# 2_FPGAIO.net
KiCad netlist of a schematic drawn in Altium Designer
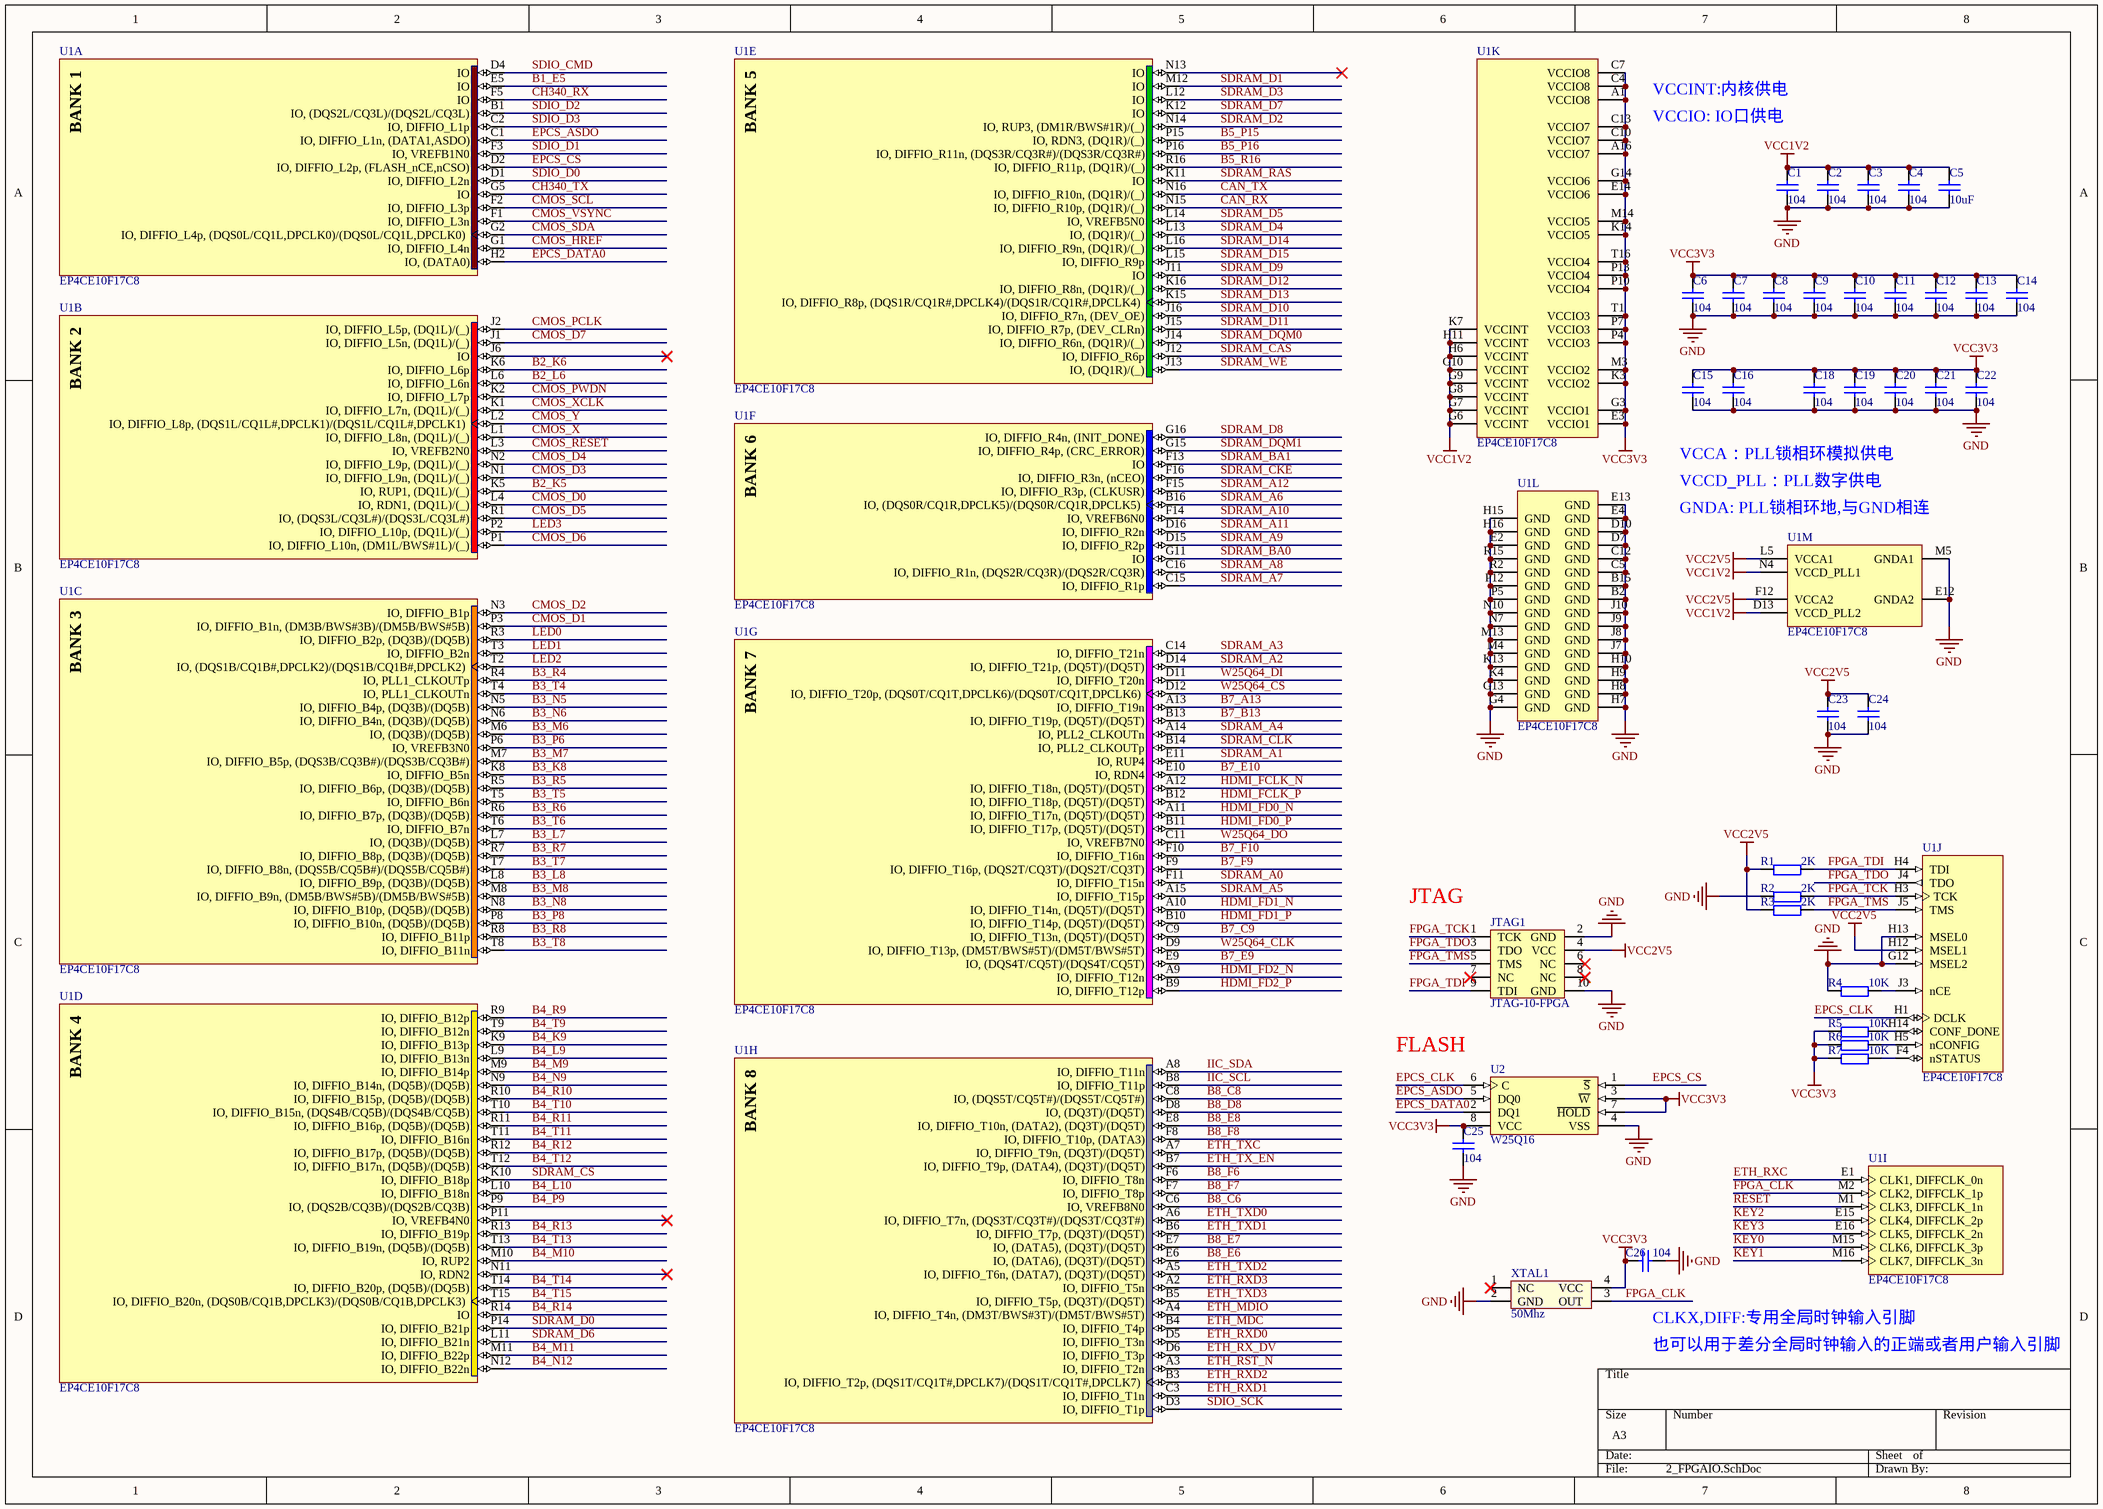
[diagram p0: 2_FPGAIO.SchDoc]

(export (version "E")
  (design (tool "Eeschema 10.0.6"))
  (components
    (comp (ref "C1")
      (value "104")
      (footprint "C 0402")
      (libsource (lib "ATK-DFPGL25G&50G_V1.3") (part "C-0603-SMD"))
    )
    (comp (ref "C2")
      (value "104")
      (footprint "C 0402")
      (libsource (lib "ATK-DFPGL25G&50G_V1.3") (part "C-0603-SMD"))
    )
    (comp (ref "C3")
      (value "104")
      (footprint "C 0402")
      (libsource (lib "ATK-DFPGL25G&50G_V1.3") (part "C-0603-SMD"))
    )
    (comp (ref "C4")
      (value "104")
      (footprint "C 0402")
      (libsource (lib "ATK-DFPGL25G&50G_V1.3") (part "C-0603-SMD"))
    )
    (comp (ref "C5")
      (value "10uF")
      (footprint "C 0402")
      (libsource (lib "ATK-DFPGL25G&50G_V1.3") (part "C-0603-SMD"))
    )
    (comp (ref "C6")
      (value "104")
      (footprint "C 0402")
      (libsource (lib "ATK-DFPGL25G&50G_V1.3") (part "C-0603-SMD"))
    )
    (comp (ref "C7")
      (value "104")
      (footprint "C 0402")
      (libsource (lib "ATK-DFPGL25G&50G_V1.3") (part "C-0603-SMD"))
    )
    (comp (ref "C8")
      (value "104")
      (footprint "C 0402")
      (libsource (lib "ATK-DFPGL25G&50G_V1.3") (part "C-0603-SMD"))
    )
    (comp (ref "C9")
      (value "104")
      (footprint "C 0402")
      (libsource (lib "ATK-DFPGL25G&50G_V1.3") (part "C-0603-SMD"))
    )
    (comp (ref "C10")
      (value "104")
      (footprint "C 0402")
      (libsource (lib "ATK-DFPGL25G&50G_V1.3") (part "C-0603-SMD"))
    )
    (comp (ref "C11")
      (value "104")
      (footprint "C 0402")
      (libsource (lib "ATK-DFPGL25G&50G_V1.3") (part "C-0603-SMD"))
    )
    (comp (ref "C12")
      (value "104")
      (footprint "C 0402")
      (libsource (lib "ATK-DFPGL25G&50G_V1.3") (part "C-0603-SMD"))
    )
    (comp (ref "C13")
      (value "104")
      (footprint "C 0402")
      (libsource (lib "ATK-DFPGL25G&50G_V1.3") (part "C-0603-SMD"))
    )
    (comp (ref "C14")
      (value "104")
      (footprint "C 0402")
      (libsource (lib "ATK-DFPGL25G&50G_V1.3") (part "C-0603-SMD"))
    )
    (comp (ref "C15")
      (value "104")
      (footprint "C 0402")
      (libsource (lib "ATK-DFPGL25G&50G_V1.3") (part "C-0603-SMD"))
    )
    (comp (ref "C16")
      (value "104")
      (footprint "C 0402")
      (libsource (lib "ATK-DFPGL25G&50G_V1.3") (part "C-0603-SMD"))
    )
    (comp (ref "C18")
      (value "104")
      (footprint "C 0402")
      (libsource (lib "ATK-DFPGL25G&50G_V1.3") (part "C-0603-SMD"))
    )
    (comp (ref "C19")
      (value "104")
      (footprint "C 0402")
      (libsource (lib "ATK-DFPGL25G&50G_V1.3") (part "C-0603-SMD"))
    )
    (comp (ref "C20")
      (value "104")
      (footprint "C 0402")
      (libsource (lib "ATK-DFPGL25G&50G_V1.3") (part "C-0603-SMD"))
    )
    (comp (ref "C21")
      (value "104")
      (footprint "C 0402")
      (libsource (lib "ATK-DFPGL25G&50G_V1.3") (part "C-0603-SMD"))
    )
    (comp (ref "C22")
      (value "104")
      (footprint "C 0402")
      (libsource (lib "ATK-DFPGL25G&50G_V1.3") (part "C-0603-SMD"))
    )
    (comp (ref "C23")
      (value "104")
      (footprint "C 0402")
      (libsource (lib "ATK-DFPGL25G&50G_V1.3") (part "C-0603-SMD"))
    )
    (comp (ref "C24")
      (value "104")
      (footprint "C 0402")
      (libsource (lib "ATK-DFPGL25G&50G_V1.3") (part "C-0603-SMD"))
    )
    (comp (ref "C25")
      (value "104")
      (footprint "C 0603")
      (libsource (lib "ATK-DFPGL25G&50G_V1.3") (part "C-0603-SMD"))
    )
    (comp (ref "C26")
      (value "104")
      (footprint "C 0603")
      (libsource (lib "ATK-DFPGL25G&50G_V1.3") (part "C-0603-SMD"))
    )
    (comp (ref "JTAG1")
      (value "JTAG-10-FPGA")
      (footprint "JTAG座_弯角_2x5")
      (libsource (lib "PIONEER") (part "JTAG-10-FPGA"))
    )
    (comp (ref "R1") (value "2K") (footprint "R 0402") (libsource (lib "PIONEER") (part "R")))
    (comp (ref "R2") (value "2K") (footprint "R 0402") (libsource (lib "PIONEER") (part "R")))
    (comp (ref "R3") (value "2K") (footprint "R 0402") (libsource (lib "PIONEER") (part "R")))
    (comp (ref "R4") (value "10K") (footprint "R 0402") (libsource (lib "PIONEER") (part "R")))
    (comp (ref "R5") (value "10K") (footprint "R 0402") (libsource (lib "PIONEER") (part "R")))
    (comp (ref "R6") (value "10K") (footprint "R 0402") (libsource (lib "PIONEER") (part "R")))
    (comp (ref "R7") (value "10K") (footprint "R 0402") (libsource (lib "PIONEER") (part "R")))
    (comp (ref "U1")
      (value "EP4CE10F17C8")
      (footprint "FBGA256")
      (fields (field (name "PUBLISHER") "Altium Limited"))
      (libsource (lib "PIONEER") (part "EP4CE6F17C8"))
    )
    (comp (ref "U2")
      (value "W25Q16")
      (footprint "SOIC-8_L5.3-W5.3-P1.27-LS8.0-BL")
      (description "16 Mb (x1) Automotive Serial NOR Flash Memory, 75 MHz, 2.7 to 3.6 V, 8-pin SO8")
      (fields (field (name "VOLTAGE") "2.7V-3.6V爭ISHIDDEN=T¦") (field (name "MANUFACTURER") "Micron"))
      (libsource (lib "PIONEER") (part "M25P16"))
    )
    (comp (ref "XTAL1")
      (value "50Mhz")
      (footprint "XTAL3225")
      (description "有源晶振")
      (libsource (lib "PIONEER") (part "XTAL_S"))
    )
  )
  (nets
    (net (code "1") (name "/B1_E5") (class "Default")
      (node (ref "U1") (pin "E5") (pinfunction "IO_E5") (pintype "bidirectional"))
    )
    (net (code "2") (name "/B2_K5") (class "Default")
      (node (ref "U1") (pin "K5") (pinfunction "IO,_RUP1,_(DQ1L)/(_)_K5") (pintype "bidirectional"))
    )
    (net (code "3") (name "/B2_K6") (class "Default")
      (node (ref "U1") (pin "K6") (pinfunction "IO,_DIFFIO_L6p_K6") (pintype "bidirectional"))
    )
    (net (code "4") (name "/B2_L6") (class "Default")
      (node (ref "U1") (pin "L6") (pinfunction "IO,_DIFFIO_L6n_L6") (pintype "bidirectional"))
    )
    (net (code "5") (name "/B3_K8") (class "Default")
      (node (ref "U1") (pin "K8") (pinfunction "IO,_DIFFIO_B5n_K8") (pintype "bidirectional"))
    )
    (net (code "6") (name "/B3_L7") (class "Default")
      (node (ref "U1") (pin "L7") (pinfunction "IO,_(DQ3B)/(DQ5B)_L7") (pintype "bidirectional"))
    )
    (net (code "7") (name "/B3_L8") (class "Default")
      (node (ref "U1") (pin "L8") (pinfunction "IO,_DIFFIO_B9p,_(DQ3B)/(DQ5B)_L8") (pintype "bidirectional"))
    )
    (net (code "8") (name "/B3_M6") (class "Default")
      (node (ref "U1") (pin "M6") (pinfunction "IO,_(DQ3B)/(DQ5B)_M6") (pintype "bidirectional"))
    )
    (net (code "9") (name "/B3_M7") (class "Default")
      (node (ref "U1") (pin "M7") (pinfunction "IO,_DIFFIO_B5p,_(DQS3B/CQ3B#)/(DQS3B/CQ3B#)_M7") (pintype "bidirectional"))
    )
    (net (code "10") (name "/B3_M8") (class "Default")
      (node (ref "U1") (pin "M8") (pinfunction "IO,_DIFFIO_B9n,_(DM5B/BWS#5B)/(DM5B/BWS#5B)_M8") (pintype "bidirectional"))
    )
    (net (code "11") (name "/B3_N5") (class "Default")
      (node (ref "U1") (pin "N5") (pinfunction "IO,_DIFFIO_B4p,_(DQ3B)/(DQ5B)_N5") (pintype "bidirectional"))
    )
    (net (code "12") (name "/B3_N6") (class "Default")
      (node (ref "U1") (pin "N6") (pinfunction "IO,_DIFFIO_B4n,_(DQ3B)/(DQ5B)_N6") (pintype "bidirectional"))
    )
    (net (code "13") (name "/B3_N8") (class "Default")
      (node (ref "U1") (pin "N8") (pinfunction "IO,_DIFFIO_B10p,_(DQ5B)/(DQ5B)_N8") (pintype "bidirectional"))
    )
    (net (code "14") (name "/B3_P6") (class "Default")
      (node (ref "U1") (pin "P6") (pinfunction "IO,_VREFB3N0_P6") (pintype "bidirectional"))
    )
    (net (code "15") (name "/B3_P8") (class "Default")
      (node (ref "U1") (pin "P8") (pinfunction "IO,_DIFFIO_B10n,_(DQ5B)/(DQ5B)_P8") (pintype "bidirectional"))
    )
    (net (code "16") (name "/B3_R4") (class "Default")
      (node (ref "U1") (pin "R4") (pinfunction "IO,_PLL1_CLKOUTp_R4") (pintype "bidirectional"))
    )
    (net (code "17") (name "/B3_R5") (class "Default")
      (node (ref "U1") (pin "R5") (pinfunction "IO,_DIFFIO_B6p,_(DQ3B)/(DQ5B)_R5") (pintype "bidirectional"))
    )
    (net (code "18") (name "/B3_R6") (class "Default")
      (node (ref "U1") (pin "R6") (pinfunction "IO,_DIFFIO_B7p,_(DQ3B)/(DQ5B)_R6") (pintype "bidirectional"))
    )
    (net (code "19") (name "/B3_R7") (class "Default")
      (node (ref "U1") (pin "R7") (pinfunction "IO,_DIFFIO_B8p,_(DQ3B)/(DQ5B)_R7") (pintype "bidirectional"))
    )
    (net (code "20") (name "/B3_R8") (class "Default")
      (node (ref "U1") (pin "R8") (pinfunction "IO,_DIFFIO_B11p_R8") (pintype "bidirectional"))
    )
    (net (code "21") (name "/B3_T4") (class "Default")
      (node (ref "U1") (pin "T4") (pinfunction "IO,_PLL1_CLKOUTn_T4") (pintype "bidirectional"))
    )
    (net (code "22") (name "/B3_T5") (class "Default")
      (node (ref "U1") (pin "T5") (pinfunction "IO,_DIFFIO_B6n_T5") (pintype "bidirectional"))
    )
    (net (code "23") (name "/B3_T6") (class "Default")
      (node (ref "U1") (pin "T6") (pinfunction "IO,_DIFFIO_B7n_T6") (pintype "bidirectional"))
    )
    (net (code "24") (name "/B3_T7") (class "Default")
      (node (ref "U1") (pin "T7") (pinfunction "IO,_DIFFIO_B8n,_(DQS5B/CQ5B#)/(DQS5B/CQ5B#)_T7") (pintype "bidirectional"))
    )
    (net (code "25") (name "/B3_T8") (class "Default")
      (node (ref "U1") (pin "T8") (pinfunction "IO,_DIFFIO_B11n_T8") (pintype "bidirectional"))
    )
    (net (code "26") (name "/B4_K9") (class "Default")
      (node (ref "U1") (pin "K9") (pinfunction "IO,_DIFFIO_B13p_K9") (pintype "bidirectional"))
    )
    (net (code "27") (name "/B4_L9") (class "Default")
      (node (ref "U1") (pin "L9") (pinfunction "IO,_DIFFIO_B13n_L9") (pintype "bidirectional"))
    )
    (net (code "28") (name "/B4_L10") (class "Default")
      (node (ref "U1") (pin "L10") (pinfunction "IO,_DIFFIO_B18n_L10") (pintype "bidirectional"))
    )
    (net (code "29") (name "/B4_M9") (class "Default")
      (node (ref "U1") (pin "M9") (pinfunction "IO,_DIFFIO_B14p_M9") (pintype "bidirectional"))
    )
    (net (code "30") (name "/B4_M10") (class "Default")
      (node (ref "U1") (pin "M10") (pinfunction "IO,_RUP2_M10") (pintype "bidirectional"))
    )
    (net (code "31") (name "/B4_M11") (class "Default")
      (node (ref "U1") (pin "M11") (pinfunction "IO,_DIFFIO_B22p_M11") (pintype "bidirectional"))
    )
    (net (code "32") (name "/B4_N9") (class "Default")
      (node (ref "U1") (pin "N9") (pinfunction "IO,_DIFFIO_B14n,_(DQ5B)/(DQ5B)_N9") (pintype "bidirectional"))
    )
    (net (code "33") (name "/B4_N12") (class "Default")
      (node (ref "U1") (pin "N12") (pinfunction "IO,_DIFFIO_B22n_N12") (pintype "bidirectional"))
    )
    (net (code "34") (name "/B4_P9") (class "Default")
      (node (ref "U1") (pin "P9") (pinfunction "IO,_(DQS2B/CQ3B)/(DQS2B/CQ3B)_P9") (pintype "bidirectional"))
    )
    (net (code "35") (name "/B4_R9") (class "Default")
      (node (ref "U1") (pin "R9") (pinfunction "IO,_DIFFIO_B12p_R9") (pintype "bidirectional"))
    )
    (net (code "36") (name "/B4_R10") (class "Default")
      (node (ref "U1") (pin "R10") (pinfunction "IO,_DIFFIO_B15p,_(DQ5B)/(DQ5B)_R10") (pintype "bidirectional"))
    )
    (net (code "37") (name "/B4_R11") (class "Default")
      (node (ref "U1") (pin "R11") (pinfunction "IO,_DIFFIO_B16p,_(DQ5B)/(DQ5B)_R11") (pintype "bidirectional"))
    )
    (net (code "38") (name "/B4_R12") (class "Default")
      (node (ref "U1") (pin "R12") (pinfunction "IO,_DIFFIO_B17p,_(DQ5B)/(DQ5B)_R12") (pintype "bidirectional"))
    )
    (net (code "39") (name "/B4_R13") (class "Default")
      (node (ref "U1") (pin "R13") (pinfunction "IO,_DIFFIO_B19p_R13") (pintype "bidirectional"))
    )
    (net (code "40") (name "/B4_R14") (class "Default")
      (node (ref "U1") (pin "R14") (pinfunction "IO_R14") (pintype "bidirectional"))
    )
    (net (code "41") (name "/B4_T9") (class "Default")
      (node (ref "U1") (pin "T9") (pinfunction "IO,_DIFFIO_B12n_T9") (pintype "bidirectional"))
    )
    (net (code "42") (name "/B4_T10") (class "Default")
      (node (ref "U1") (pin "T10") (pinfunction "IO,_DIFFIO_B15n,_(DQS4B/CQ5B)/(DQS4B/CQ5B)_T10") (pintype "bidirectional"))
    )
    (net (code "43") (name "/B4_T11") (class "Default")
      (node (ref "U1") (pin "T11") (pinfunction "IO,_DIFFIO_B16n_T11") (pintype "bidirectional"))
    )
    (net (code "44") (name "/B4_T12") (class "Default")
      (node (ref "U1") (pin "T12") (pinfunction "IO,_DIFFIO_B17n,_(DQ5B)/(DQ5B)_T12") (pintype "bidirectional"))
    )
    (net (code "45") (name "/B4_T13") (class "Default")
      (node (ref "U1") (pin "T13") (pinfunction "IO,_DIFFIO_B19n,_(DQ5B)/(DQ5B)_T13") (pintype "bidirectional"))
    )
    (net (code "46") (name "/B4_T14") (class "Default")
      (node (ref "U1") (pin "T14") (pinfunction "IO,_DIFFIO_B20p,_(DQ5B)/(DQ5B)_T14") (pintype "bidirectional"))
    )
    (net (code "47") (name "/B4_T15") (class "Default")
      (node (ref "U1") (pin "T15") (pinfunction "IO,_DIFFIO_B20n,_(DQS0B/CQ1B,DPCLK3)/(DQS0B/CQ1B,DPCLK3)_T15") (pintype "bidirectional"))
    )
    (net (code "48") (name "/B5_P15") (class "Default")
      (node (ref "U1") (pin "P15") (pinfunction "IO,_RDN3,_(DQ1R)/(_)_P15") (pintype "bidirectional"))
    )
    (net (code "49") (name "/B5_P16") (class "Default")
      (node (ref "U1") (pin "P16") (pinfunction "IO,_DIFFIO_R11n,_(DQS3R/CQ3R#)/(DQS3R/CQ3R#)_P16") (pintype "bidirectional"))
    )
    (net (code "50") (name "/B5_R16") (class "Default")
      (node (ref "U1") (pin "R16") (pinfunction "IO,_DIFFIO_R11p,_(DQ1R)/(_)_R16") (pintype "bidirectional"))
    )
    (net (code "51") (name "/B7_A13") (class "Default")
      (node (ref "U1") (pin "A13") (pinfunction "IO,_DIFFIO_T19n_A13") (pintype "bidirectional"))
    )
    (net (code "52") (name "/B7_B13") (class "Default")
      (node (ref "U1") (pin "B13") (pinfunction "IO,_DIFFIO_T19p,_(DQ5T)/(DQ5T)_B13") (pintype "bidirectional"))
    )
    (net (code "53") (name "/B7_C9") (class "Default")
      (node (ref "U1") (pin "C9") (pinfunction "IO,_DIFFIO_T13n,_(DQ5T)/(DQ5T)_C9") (pintype "bidirectional"))
    )
    (net (code "54") (name "/B7_E9") (class "Default")
      (node (ref "U1") (pin "E9") (pinfunction "IO,_(DQS4T/CQ5T)/(DQS4T/CQ5T)_E9") (pintype "bidirectional"))
    )
    (net (code "55") (name "/B7_E10") (class "Default")
      (node (ref "U1") (pin "E10") (pinfunction "IO,_RDN4_E10") (pintype "bidirectional"))
    )
    (net (code "56") (name "/B7_F9") (class "Default")
      (node (ref "U1") (pin "F9") (pinfunction "IO,_DIFFIO_T16p,_(DQS2T/CQ3T)/(DQS2T/CQ3T)_F9") (pintype "bidirectional"))
    )
    (net (code "57") (name "/B7_F10") (class "Default")
      (node (ref "U1") (pin "F10") (pinfunction "IO,_DIFFIO_T16n_F10") (pintype "bidirectional"))
    )
    (net (code "58") (name "/B8_C6") (class "Default")
      (node (ref "U1") (pin "C6") (pinfunction "IO,_VREFB8N0_C6") (pintype "bidirectional"))
    )
    (net (code "59") (name "/B8_C8") (class "Default")
      (node (ref "U1") (pin "C8") (pinfunction "IO,_(DQS5T/CQ5T#)/(DQS5T/CQ5T#)_C8") (pintype "bidirectional"))
    )
    (net (code "60") (name "/B8_D8") (class "Default")
      (node (ref "U1") (pin "D8") (pinfunction "IO,_(DQ3T)/(DQ5T)_D8") (pintype "bidirectional"))
    )
    (net (code "61") (name "/B8_E6") (class "Default")
      (node (ref "U1") (pin "E6") (pinfunction "IO,_(DATA6),_(DQ3T)/(DQ5T)_E6") (pintype "bidirectional"))
    )
    (net (code "62") (name "/B8_E7") (class "Default")
      (node (ref "U1") (pin "E7") (pinfunction "IO,_(DATA5),_(DQ3T)/(DQ5T)_E7") (pintype "bidirectional"))
    )
    (net (code "63") (name "/B8_E8") (class "Default")
      (node (ref "U1") (pin "E8") (pinfunction "IO,_DIFFIO_T10n,_(DATA2),_(DQ3T)/(DQ5T)_E8") (pintype "bidirectional"))
    )
    (net (code "64") (name "/B8_F6") (class "Default")
      (node (ref "U1") (pin "F6") (pinfunction "IO,_DIFFIO_T8n_F6") (pintype "bidirectional"))
    )
    (net (code "65") (name "/B8_F7") (class "Default")
      (node (ref "U1") (pin "F7") (pinfunction "IO,_DIFFIO_T8p_F7") (pintype "bidirectional"))
    )
    (net (code "66") (name "/B8_F8") (class "Default")
      (node (ref "U1") (pin "F8") (pinfunction "IO,_DIFFIO_T10p,_(DATA3)_F8") (pintype "bidirectional"))
    )
    (net (code "67") (name "/CAN_RX") (class "Default")
      (node (ref "U1") (pin "N15") (pinfunction "IO,_DIFFIO_R10p,_(DQ1R)/(_)_N15") (pintype "bidirectional"))
    )
    (net (code "68") (name "/CAN_TX") (class "Default")
      (node (ref "U1") (pin "N16") (pinfunction "IO,_DIFFIO_R10n,_(DQ1R)/(_)_N16") (pintype "bidirectional"))
    )
    (net (code "69") (name "/CH340_RX") (class "Default")
      (node (ref "U1") (pin "F5") (pinfunction "IO_F5") (pintype "bidirectional"))
    )
    (net (code "70") (name "/CH340_TX") (class "Default")
      (node (ref "U1") (pin "G5") (pinfunction "IO_G5") (pintype "bidirectional"))
    )
    (net (code "71") (name "/CMOS_D0") (class "Default")
      (node (ref "U1") (pin "L4") (pinfunction "IO,_RDN1,_(DQ1L)/(_)_L4") (pintype "bidirectional"))
    )
    (net (code "72") (name "/CMOS_D1") (class "Default")
      (node (ref "U1") (pin "P3") (pinfunction "IO,_DIFFIO_B1n,_(DM3B/BWS#3B)/(DM5B/BWS#5B)_P3") (pintype "bidirectional"))
    )
    (net (code "73") (name "/CMOS_D2") (class "Default")
      (node (ref "U1") (pin "N3") (pinfunction "IO,_DIFFIO_B1p_N3") (pintype "bidirectional"))
    )
    (net (code "74") (name "/CMOS_D3") (class "Default")
      (node (ref "U1") (pin "N1") (pinfunction "IO,_DIFFIO_L9n,_(DQ1L)/(_)_N1") (pintype "bidirectional"))
    )
    (net (code "75") (name "/CMOS_D4") (class "Default")
      (node (ref "U1") (pin "N2") (pinfunction "IO,_DIFFIO_L9p,_(DQ1L)/(_)_N2") (pintype "bidirectional"))
    )
    (net (code "76") (name "/CMOS_D5") (class "Default")
      (node (ref "U1") (pin "R1") (pinfunction "IO,_(DQS3L/CQ3L#)/(DQS3L/CQ3L#)_R1") (pintype "bidirectional"))
    )
    (net (code "77") (name "/CMOS_D6") (class "Default")
      (node (ref "U1") (pin "P1") (pinfunction "IO,_DIFFIO_L10n,_(DM1L/BWS#1L)/(_)_P1") (pintype "bidirectional"))
    )
    (net (code "78") (name "/CMOS_D7") (class "Default")
      (node (ref "U1") (pin "J1") (pinfunction "IO,_DIFFIO_L5n,_(DQ1L)/(_)_J1") (pintype "bidirectional"))
    )
    (net (code "79") (name "/CMOS_HREF") (class "Default")
      (node (ref "U1") (pin "G1") (pinfunction "IO,_DIFFIO_L4n_G1") (pintype "bidirectional"))
    )
    (net (code "80") (name "/CMOS_PCLK") (class "Default")
      (node (ref "U1") (pin "J2") (pinfunction "IO,_DIFFIO_L5p,_(DQ1L)/(_)_J2") (pintype "bidirectional"))
    )
    (net (code "81") (name "/CMOS_PWDN") (class "Default")
      (node (ref "U1") (pin "K2") (pinfunction "IO,_DIFFIO_L7p_K2") (pintype "bidirectional"))
    )
    (net (code "82") (name "/CMOS_RESET") (class "Default")
      (node (ref "U1") (pin "L3") (pinfunction "IO,_VREFB2N0_L3") (pintype "bidirectional"))
    )
    (net (code "83") (name "/CMOS_SCL") (class "Default")
      (node (ref "U1") (pin "F2") (pinfunction "IO,_DIFFIO_L3p_F2") (pintype "bidirectional"))
    )
    (net (code "84") (name "/CMOS_SDA") (class "Default")
      (node (ref "U1") (pin "G2") (pinfunction "IO,_DIFFIO_L4p,_(DQS0L/CQ1L,DPCLK0)/(DQS0L/CQ1L,DPCLK0)_G2") (pintype "bidirectional"))
    )
    (net (code "85") (name "/CMOS_VSYNC") (class "Default")
      (node (ref "U1") (pin "F1") (pinfunction "IO,_DIFFIO_L3n_F1") (pintype "bidirectional"))
    )
    (net (code "86") (name "/CMOS_X") (class "Default")
      (node (ref "U1") (pin "L1") (pinfunction "IO,_DIFFIO_L8n,_(DQ1L)/(_)_L1") (pintype "bidirectional"))
    )
    (net (code "87") (name "/CMOS_XCLK") (class "Default")
      (node (ref "U1") (pin "K1") (pinfunction "IO,_DIFFIO_L7n,_(DQ1L)/(_)_K1") (pintype "bidirectional"))
    )
    (net (code "88") (name "/CMOS_Y") (class "Default")
      (node (ref "U1") (pin "L2") (pinfunction "IO,_DIFFIO_L8p,_(DQS1L/CQ1L#,DPCLK1)/(DQS1L/CQ1L#,DPCLK1)_L2") (pintype "bidirectional"))
    )
    (net (code "89") (name "/EPCS_ASDO") (class "Default")
      (node (ref "U1") (pin "C1") (pinfunction "IO,_DIFFIO_L1n,_(DATA1,ASDO)_C1") (pintype "bidirectional"))
      (node (ref "U2") (pin "5") (pinfunction "DQ0_5") (pintype "input"))
    )
    (net (code "90") (name "/EPCS_CLK") (class "Default")
      (node (ref "U1") (pin "H1") (pinfunction "DCLK_H1") (pintype "bidirectional"))
      (node (ref "U2") (pin "6") (pinfunction "C_6") (pintype "input"))
    )
    (net (code "91") (name "/EPCS_CS") (class "Default")
      (node (ref "U1") (pin "D2") (pinfunction "IO,_DIFFIO_L2p,_(FLASH_nCE,nCSO)_D2") (pintype "bidirectional"))
      (node (ref "U2") (pin "1") (pinfunction "~{S}_1") (pintype "input"))
    )
    (net (code "92") (name "/EPCS_DATA0") (class "Default")
      (node (ref "U1") (pin "H2") (pinfunction "IO,_(DATA0)_H2") (pintype "bidirectional"))
      (node (ref "U2") (pin "2") (pinfunction "DQ1_2") (pintype "tri_state"))
    )
    (net (code "93") (name "/ETH_MDC") (class "Default")
      (node (ref "U1") (pin "B4") (pinfunction "IO,_DIFFIO_T4p_B4") (pintype "bidirectional"))
    )
    (net (code "94") (name "/ETH_MDIO") (class "Default")
      (node (ref "U1") (pin "A4") (pinfunction "IO,_DIFFIO_T4n,_(DM3T/BWS#3T)/(DM5T/BWS#5T)_A4") (pintype "bidirectional"))
    )
    (net (code "95") (name "/ETH_RST_N") (class "Default")
      (node (ref "U1") (pin "A3") (pinfunction "IO,_DIFFIO_T2n_A3") (pintype "bidirectional"))
    )
    (net (code "96") (name "/ETH_RXC") (class "Default")
      (node (ref "U1") (pin "E1") (pinfunction "CLK1,_DIFFCLK_0n_E1") (pintype "input"))
    )
    (net (code "97") (name "/ETH_RXD0") (class "Default")
      (node (ref "U1") (pin "D5") (pinfunction "IO,_DIFFIO_T3n_D5") (pintype "bidirectional"))
    )
    (net (code "98") (name "/ETH_RXD1") (class "Default")
      (node (ref "U1") (pin "C3") (pinfunction "IO,_DIFFIO_T1n_C3") (pintype "bidirectional"))
    )
    (net (code "99") (name "/ETH_RXD2") (class "Default")
      (node (ref "U1") (pin "B3") (pinfunction "IO,_DIFFIO_T2p,_(DQS1T/CQ1T#,DPCLK7)/(DQS1T/CQ1T#,DPCLK7)_B3") (pintype "bidirectional"))
    )
    (net (code "100") (name "/ETH_RXD3") (class "Default")
      (node (ref "U1") (pin "A2") (pinfunction "IO,_DIFFIO_T5n_A2") (pintype "bidirectional"))
    )
    (net (code "101") (name "/ETH_RX_DV") (class "Default")
      (node (ref "U1") (pin "D6") (pinfunction "IO,_DIFFIO_T3p_D6") (pintype "bidirectional"))
    )
    (net (code "102") (name "/ETH_TXC") (class "Default")
      (node (ref "U1") (pin "A7") (pinfunction "IO,_DIFFIO_T9n,_(DQ3T)/(DQ5T)_A7") (pintype "bidirectional"))
    )
    (net (code "103") (name "/ETH_TXD0") (class "Default")
      (node (ref "U1") (pin "A6") (pinfunction "IO,_DIFFIO_T7n,_(DQS3T/CQ3T#)/(DQS3T/CQ3T#)_A6") (pintype "bidirectional"))
    )
    (net (code "104") (name "/ETH_TXD1") (class "Default")
      (node (ref "U1") (pin "B6") (pinfunction "IO,_DIFFIO_T7p,_(DQ3T)/(DQ5T)_B6") (pintype "bidirectional"))
    )
    (net (code "105") (name "/ETH_TXD2") (class "Default")
      (node (ref "U1") (pin "A5") (pinfunction "IO,_DIFFIO_T6n,_(DATA7),_(DQ3T)/(DQ5T)_A5") (pintype "bidirectional"))
    )
    (net (code "106") (name "/ETH_TXD3") (class "Default")
      (node (ref "U1") (pin "B5") (pinfunction "IO,_DIFFIO_T5p,_(DQ3T)/(DQ5T)_B5") (pintype "bidirectional"))
    )
    (net (code "107") (name "/ETH_TX_EN") (class "Default")
      (node (ref "U1") (pin "B7") (pinfunction "IO,_DIFFIO_T9p,_(DATA4),_(DQ3T)/(DQ5T)_B7") (pintype "bidirectional"))
    )
    (net (code "108") (name "/FPGA_CLK") (class "Default")
      (node (ref "U1") (pin "M2") (pinfunction "CLK2,_DIFFCLK_1p_M2") (pintype "input"))
      (node (ref "XTAL1") (pin "3") (pinfunction "OUT_3") (pintype "passive"))
    )
    (net (code "109") (name "/FPGA_TCK") (class "Default")
      (node (ref "JTAG1") (pin "1") (pinfunction "TCK_1") (pintype "passive"))
      (node (ref "R2") (pin "2") (pintype "passive"))
      (node (ref "U1") (pin "H3") (pinfunction "TCK_H3") (pintype "input"))
    )
    (net (code "110") (name "/FPGA_TDI") (class "Default")
      (node (ref "JTAG1") (pin "9") (pinfunction "TDI_9") (pintype "passive"))
      (node (ref "R1") (pin "2") (pintype "passive"))
      (node (ref "U1") (pin "H4") (pinfunction "TDI_H4") (pintype "input"))
    )
    (net (code "111") (name "/FPGA_TDO") (class "Default")
      (node (ref "JTAG1") (pin "3") (pinfunction "TDO_3") (pintype "passive"))
      (node (ref "U1") (pin "J4") (pinfunction "TDO_J4") (pintype "output"))
    )
    (net (code "112") (name "/FPGA_TMS") (class "Default")
      (node (ref "JTAG1") (pin "5") (pinfunction "TMS_5") (pintype "passive"))
      (node (ref "R3") (pin "2") (pintype "passive"))
      (node (ref "U1") (pin "J5") (pinfunction "TMS_J5") (pintype "input"))
    )
    (net (code "113") (name "/HDMI_FCLK_N") (class "Default")
      (node (ref "U1") (pin "A12") (pinfunction "IO,_DIFFIO_T18n,_(DQ5T)/(DQ5T)_A12") (pintype "bidirectional"))
    )
    (net (code "114") (name "/HDMI_FCLK_P") (class "Default")
      (node (ref "U1") (pin "B12") (pinfunction "IO,_DIFFIO_T18p,_(DQ5T)/(DQ5T)_B12") (pintype "bidirectional"))
    )
    (net (code "115") (name "/HDMI_FD0_N") (class "Default")
      (node (ref "U1") (pin "A11") (pinfunction "IO,_DIFFIO_T17n,_(DQ5T)/(DQ5T)_A11") (pintype "bidirectional"))
    )
    (net (code "116") (name "/HDMI_FD0_P") (class "Default")
      (node (ref "U1") (pin "B11") (pinfunction "IO,_DIFFIO_T17p,_(DQ5T)/(DQ5T)_B11") (pintype "bidirectional"))
    )
    (net (code "117") (name "/HDMI_FD1_N") (class "Default")
      (node (ref "U1") (pin "A10") (pinfunction "IO,_DIFFIO_T14n,_(DQ5T)/(DQ5T)_A10") (pintype "bidirectional"))
    )
    (net (code "118") (name "/HDMI_FD1_P") (class "Default")
      (node (ref "U1") (pin "B10") (pinfunction "IO,_DIFFIO_T14p,_(DQ5T)/(DQ5T)_B10") (pintype "bidirectional"))
    )
    (net (code "119") (name "/HDMI_FD2_N") (class "Default")
      (node (ref "U1") (pin "A9") (pinfunction "IO,_DIFFIO_T12n_A9") (pintype "bidirectional"))
    )
    (net (code "120") (name "/HDMI_FD2_P") (class "Default")
      (node (ref "U1") (pin "B9") (pinfunction "IO,_DIFFIO_T12p_B9") (pintype "bidirectional"))
    )
    (net (code "121") (name "/IIC_SCL") (class "Default")
      (node (ref "U1") (pin "B8") (pinfunction "IO,_DIFFIO_T11p_B8") (pintype "bidirectional"))
    )
    (net (code "122") (name "/IIC_SDA") (class "Default")
      (node (ref "U1") (pin "A8") (pinfunction "IO,_DIFFIO_T11n_A8") (pintype "bidirectional"))
    )
    (net (code "123") (name "/KEY0") (class "Default")
      (node (ref "U1") (pin "M15") (pinfunction "CLK6,_DIFFCLK_3p_M15") (pintype "input"))
    )
    (net (code "124") (name "/KEY1") (class "Default")
      (node (ref "U1") (pin "M16") (pinfunction "CLK7,_DIFFCLK_3n_M16") (pintype "input"))
    )
    (net (code "125") (name "/KEY2") (class "Default")
      (node (ref "U1") (pin "E15") (pinfunction "CLK4,_DIFFCLK_2p_E15") (pintype "input"))
    )
    (net (code "126") (name "/KEY3") (class "Default")
      (node (ref "U1") (pin "E16") (pinfunction "CLK5,_DIFFCLK_2n_E16") (pintype "input"))
    )
    (net (code "127") (name "/LED0") (class "Default")
      (node (ref "U1") (pin "R3") (pinfunction "IO,_DIFFIO_B2p,_(DQ3B)/(DQ5B)_R3") (pintype "bidirectional"))
    )
    (net (code "128") (name "/LED1") (class "Default")
      (node (ref "U1") (pin "T3") (pinfunction "IO,_DIFFIO_B2n_T3") (pintype "bidirectional"))
    )
    (net (code "129") (name "/LED2") (class "Default")
      (node (ref "U1") (pin "T2") (pinfunction "IO,_(DQS1B/CQ1B#,DPCLK2)/(DQS1B/CQ1B#,DPCLK2)_T2") (pintype "bidirectional"))
    )
    (net (code "130") (name "/LED3") (class "Default")
      (node (ref "U1") (pin "P2") (pinfunction "IO,_DIFFIO_L10p,_(DQ1L)/(_)_P2") (pintype "bidirectional"))
    )
    (net (code "131") (name "/RESET") (class "Default")
      (node (ref "U1") (pin "M1") (pinfunction "CLK3,_DIFFCLK_1n_M1") (pintype "input"))
    )
    (net (code "132") (name "/SDIO_CMD") (class "Default")
      (node (ref "U1") (pin "D4") (pinfunction "IO_D4") (pintype "bidirectional"))
    )
    (net (code "133") (name "/SDIO_D0") (class "Default")
      (node (ref "U1") (pin "D1") (pinfunction "IO,_DIFFIO_L2n_D1") (pintype "bidirectional"))
    )
    (net (code "134") (name "/SDIO_D1") (class "Default")
      (node (ref "U1") (pin "F3") (pinfunction "IO,_VREFB1N0_F3") (pintype "bidirectional"))
    )
    (net (code "135") (name "/SDIO_D2") (class "Default")
      (node (ref "U1") (pin "B1") (pinfunction "IO,_(DQS2L/CQ3L)/(DQS2L/CQ3L)_B1") (pintype "bidirectional"))
    )
    (net (code "136") (name "/SDIO_D3") (class "Default")
      (node (ref "U1") (pin "C2") (pinfunction "IO,_DIFFIO_L1p_C2") (pintype "bidirectional"))
    )
    (net (code "137") (name "/SDIO_SCK") (class "Default")
      (node (ref "U1") (pin "D3") (pinfunction "IO,_DIFFIO_T1p_D3") (pintype "bidirectional"))
    )
    (net (code "138") (name "/SDRAM_A0") (class "Default")
      (node (ref "U1") (pin "F11") (pinfunction "IO,_DIFFIO_T15n_F11") (pintype "bidirectional"))
    )
    (net (code "139") (name "/SDRAM_A1") (class "Default")
      (node (ref "U1") (pin "E11") (pinfunction "IO,_RUP4_E11") (pintype "bidirectional"))
    )
    (net (code "140") (name "/SDRAM_A2") (class "Default")
      (node (ref "U1") (pin "D14") (pinfunction "IO,_DIFFIO_T21p,_(DQ5T)/(DQ5T)_D14") (pintype "bidirectional"))
    )
    (net (code "141") (name "/SDRAM_A3") (class "Default")
      (node (ref "U1") (pin "C14") (pinfunction "IO,_DIFFIO_T21n_C14") (pintype "bidirectional"))
    )
    (net (code "142") (name "/SDRAM_A4") (class "Default")
      (node (ref "U1") (pin "A14") (pinfunction "IO,_PLL2_CLKOUTn_A14") (pintype "bidirectional"))
    )
    (net (code "143") (name "/SDRAM_A5") (class "Default")
      (node (ref "U1") (pin "A15") (pinfunction "IO,_DIFFIO_T15p_A15") (pintype "bidirectional"))
    )
    (net (code "144") (name "/SDRAM_A6") (class "Default")
      (node (ref "U1") (pin "B16") (pinfunction "IO,_(DQS0R/CQ1R,DPCLK5)/(DQS0R/CQ1R,DPCLK5)_B16") (pintype "bidirectional"))
    )
    (net (code "145") (name "/SDRAM_A7") (class "Default")
      (node (ref "U1") (pin "C15") (pinfunction "IO,_DIFFIO_R1p_C15") (pintype "bidirectional"))
    )
    (net (code "146") (name "/SDRAM_A8") (class "Default")
      (node (ref "U1") (pin "C16") (pinfunction "IO,_DIFFIO_R1n,_(DQS2R/CQ3R)/(DQS2R/CQ3R)_C16") (pintype "bidirectional"))
    )
    (net (code "147") (name "/SDRAM_A9") (class "Default")
      (node (ref "U1") (pin "D15") (pinfunction "IO,_DIFFIO_R2p_D15") (pintype "bidirectional"))
    )
    (net (code "148") (name "/SDRAM_A10") (class "Default")
      (node (ref "U1") (pin "F14") (pinfunction "IO,_VREFB6N0_F14") (pintype "bidirectional"))
    )
    (net (code "149") (name "/SDRAM_A11") (class "Default")
      (node (ref "U1") (pin "D16") (pinfunction "IO,_DIFFIO_R2n_D16") (pintype "bidirectional"))
    )
    (net (code "150") (name "/SDRAM_A12") (class "Default")
      (node (ref "U1") (pin "F15") (pinfunction "IO,_DIFFIO_R3p,_(CLKUSR)_F15") (pintype "bidirectional"))
    )
    (net (code "151") (name "/SDRAM_BA0") (class "Default")
      (node (ref "U1") (pin "G11") (pinfunction "IO_G11") (pintype "bidirectional"))
    )
    (net (code "152") (name "/SDRAM_BA1") (class "Default")
      (node (ref "U1") (pin "F13") (pinfunction "IO_F13") (pintype "bidirectional"))
    )
    (net (code "153") (name "/SDRAM_CAS") (class "Default")
      (node (ref "U1") (pin "J12") (pinfunction "IO,_DIFFIO_R6p_J12") (pintype "bidirectional"))
    )
    (net (code "154") (name "/SDRAM_CKE") (class "Default")
      (node (ref "U1") (pin "F16") (pinfunction "IO,_DIFFIO_R3n,_(nCEO)_F16") (pintype "bidirectional"))
    )
    (net (code "155") (name "/SDRAM_CLK") (class "Default")
      (node (ref "U1") (pin "B14") (pinfunction "IO,_PLL2_CLKOUTp_B14") (pintype "bidirectional"))
    )
    (net (code "156") (name "/SDRAM_CS") (class "Default")
      (node (ref "U1") (pin "K10") (pinfunction "IO,_DIFFIO_B18p_K10") (pintype "bidirectional"))
    )
    (net (code "157") (name "/SDRAM_D0") (class "Default")
      (node (ref "U1") (pin "P14") (pinfunction "IO,_DIFFIO_B21p_P14") (pintype "bidirectional"))
    )
    (net (code "158") (name "/SDRAM_D1") (class "Default")
      (node (ref "U1") (pin "M12") (pinfunction "IO_M12") (pintype "bidirectional"))
    )
    (net (code "159") (name "/SDRAM_D2") (class "Default")
      (node (ref "U1") (pin "N14") (pinfunction "IO,_RUP3,_(DM1R/BWS#1R)/(_)_N14") (pintype "bidirectional"))
    )
    (net (code "160") (name "/SDRAM_D3") (class "Default")
      (node (ref "U1") (pin "L12") (pinfunction "IO_L12") (pintype "bidirectional"))
    )
    (net (code "161") (name "/SDRAM_D4") (class "Default")
      (node (ref "U1") (pin "L13") (pinfunction "IO,_(DQ1R)/(_)_L13") (pintype "bidirectional"))
    )
    (net (code "162") (name "/SDRAM_D5") (class "Default")
      (node (ref "U1") (pin "L14") (pinfunction "IO,_VREFB5N0_L14") (pintype "bidirectional"))
    )
    (net (code "163") (name "/SDRAM_D6") (class "Default")
      (node (ref "U1") (pin "L11") (pinfunction "IO,_DIFFIO_B21n_L11") (pintype "bidirectional"))
    )
    (net (code "164") (name "/SDRAM_D7") (class "Default")
      (node (ref "U1") (pin "K12") (pinfunction "IO_K12") (pintype "bidirectional"))
    )
    (net (code "165") (name "/SDRAM_D8") (class "Default")
      (node (ref "U1") (pin "G16") (pinfunction "IO,_DIFFIO_R4n,_(INIT_DONE)_G16") (pintype "bidirectional"))
    )
    (net (code "166") (name "/SDRAM_D9") (class "Default")
      (node (ref "U1") (pin "J11") (pinfunction "IO_J11") (pintype "bidirectional"))
    )
    (net (code "167") (name "/SDRAM_D10") (class "Default")
      (node (ref "U1") (pin "J16") (pinfunction "IO,_DIFFIO_R7n,_(DEV_OE)_J16") (pintype "bidirectional"))
    )
    (net (code "168") (name "/SDRAM_D11") (class "Default")
      (node (ref "U1") (pin "J15") (pinfunction "IO,_DIFFIO_R7p,_(DEV_CLRn)_J15") (pintype "bidirectional"))
    )
    (net (code "169") (name "/SDRAM_D12") (class "Default")
      (node (ref "U1") (pin "K16") (pinfunction "IO,_DIFFIO_R8n,_(DQ1R)/(_)_K16") (pintype "bidirectional"))
    )
    (net (code "170") (name "/SDRAM_D13") (class "Default")
      (node (ref "U1") (pin "K15") (pinfunction "IO,_DIFFIO_R8p,_(DQS1R/CQ1R#,DPCLK4)/(DQS1R/CQ1R#,DPCLK4)_K15") (pintype "bidirectional"))
    )
    (net (code "171") (name "/SDRAM_D14") (class "Default")
      (node (ref "U1") (pin "L16") (pinfunction "IO,_DIFFIO_R9n,_(DQ1R)/(_)_L16") (pintype "bidirectional"))
    )
    (net (code "172") (name "/SDRAM_D15") (class "Default")
      (node (ref "U1") (pin "L15") (pinfunction "IO,_DIFFIO_R9p_L15") (pintype "bidirectional"))
    )
    (net (code "173") (name "/SDRAM_DQM0") (class "Default")
      (node (ref "U1") (pin "J14") (pinfunction "IO,_DIFFIO_R6n,_(DQ1R)/(_)_J14") (pintype "bidirectional"))
    )
    (net (code "174") (name "/SDRAM_DQM1") (class "Default")
      (node (ref "U1") (pin "G15") (pinfunction "IO,_DIFFIO_R4p,_(CRC_ERROR)_G15") (pintype "bidirectional"))
    )
    (net (code "175") (name "/SDRAM_RAS") (class "Default")
      (node (ref "U1") (pin "K11") (pinfunction "IO_K11") (pintype "bidirectional"))
    )
    (net (code "176") (name "/SDRAM_WE") (class "Default")
      (node (ref "U1") (pin "J13") (pinfunction "IO,_(DQ1R)/(_)_J13") (pintype "bidirectional"))
    )
    (net (code "177") (name "/W25Q64_CLK") (class "Default")
      (node (ref "U1") (pin "D9") (pinfunction "IO,_DIFFIO_T13p,_(DM5T/BWS#5T)/(DM5T/BWS#5T)_D9") (pintype "bidirectional"))
    )
    (net (code "178") (name "/W25Q64_CS") (class "Default")
      (node (ref "U1") (pin "D12") (pinfunction "IO,_DIFFIO_T20p,_(DQS0T/CQ1T,DPCLK6)/(DQS0T/CQ1T,DPCLK6)_D12") (pintype "bidirectional"))
    )
    (net (code "179") (name "/W25Q64_DI") (class "Default")
      (node (ref "U1") (pin "D11") (pinfunction "IO,_DIFFIO_T20n_D11") (pintype "bidirectional"))
    )
    (net (code "180") (name "/W25Q64_DO") (class "Default")
      (node (ref "U1") (pin "C11") (pinfunction "IO,_VREFB7N0_C11") (pintype "bidirectional"))
    )
    (net (code "181") (name "GND") (class "Default")
      (node (ref "C1") (pin "2") (pinfunction "2_2") (pintype "passive"))
      (node (ref "C10") (pin "2") (pinfunction "2_2") (pintype "passive"))
      (node (ref "C11") (pin "2") (pinfunction "2_2") (pintype "passive"))
      (node (ref "C12") (pin "2") (pinfunction "2_2") (pintype "passive"))
      (node (ref "C13") (pin "2") (pinfunction "2_2") (pintype "passive"))
      (node (ref "C14") (pin "2") (pinfunction "2_2") (pintype "passive"))
      (node (ref "C15") (pin "2") (pinfunction "2_2") (pintype "passive"))
      (node (ref "C16") (pin "2") (pinfunction "2_2") (pintype "passive"))
      (node (ref "C18") (pin "2") (pinfunction "2_2") (pintype "passive"))
      (node (ref "C19") (pin "2") (pinfunction "2_2") (pintype "passive"))
      (node (ref "C2") (pin "2") (pinfunction "2_2") (pintype "passive"))
      (node (ref "C20") (pin "2") (pinfunction "2_2") (pintype "passive"))
      (node (ref "C21") (pin "2") (pinfunction "2_2") (pintype "passive"))
      (node (ref "C22") (pin "2") (pinfunction "2_2") (pintype "passive"))
      (node (ref "C23") (pin "2") (pinfunction "2_2") (pintype "passive"))
      (node (ref "C24") (pin "2") (pinfunction "2_2") (pintype "passive"))
      (node (ref "C25") (pin "2") (pinfunction "2_2") (pintype "passive"))
      (node (ref "C26") (pin "2") (pinfunction "2_2") (pintype "passive"))
      (node (ref "C3") (pin "2") (pinfunction "2_2") (pintype "passive"))
      (node (ref "C4") (pin "2") (pinfunction "2_2") (pintype "passive"))
      (node (ref "C5") (pin "2") (pinfunction "2_2") (pintype "passive"))
      (node (ref "C6") (pin "2") (pinfunction "2_2") (pintype "passive"))
      (node (ref "C7") (pin "2") (pinfunction "2_2") (pintype "passive"))
      (node (ref "C8") (pin "2") (pinfunction "2_2") (pintype "passive"))
      (node (ref "C9") (pin "2") (pinfunction "2_2") (pintype "passive"))
      (node (ref "JTAG1") (pin "10") (pinfunction "GND_10") (pintype "passive"))
      (node (ref "JTAG1") (pin "2") (pinfunction "GND_2") (pintype "passive"))
      (node (ref "R2") (pin "1") (pintype "passive"))
      (node (ref "R4") (pin "1") (pintype "passive"))
      (node (ref "U1") (pin "B15") (pinfunction "GND_B15") (pintype "power_in"))
      (node (ref "U1") (pin "B2") (pinfunction "GND_B2") (pintype "power_in"))
      (node (ref "U1") (pin "C12") (pinfunction "GND_C12") (pintype "power_in"))
      (node (ref "U1") (pin "C5") (pinfunction "GND_C5") (pintype "power_in"))
      (node (ref "U1") (pin "D10") (pinfunction "GND_D10") (pintype "power_in"))
      (node (ref "U1") (pin "D7") (pinfunction "GND_D7") (pintype "power_in"))
      (node (ref "U1") (pin "E12") (pinfunction "GNDA2_E12") (pintype "power_in"))
      (node (ref "U1") (pin "E13") (pinfunction "GND_E13") (pintype "power_in"))
      (node (ref "U1") (pin "E2") (pinfunction "GND_E2") (pintype "power_in"))
      (node (ref "U1") (pin "E4") (pinfunction "GND_E4") (pintype "power_in"))
      (node (ref "U1") (pin "G12") (pinfunction "MSEL2_G12") (pintype "input"))
      (node (ref "U1") (pin "G13") (pinfunction "GND_G13") (pintype "power_in"))
      (node (ref "U1") (pin "G4") (pinfunction "GND_G4") (pintype "power_in"))
      (node (ref "U1") (pin "H10") (pinfunction "GND_H10") (pintype "power_in"))
      (node (ref "U1") (pin "H13") (pinfunction "MSEL0_H13") (pintype "input"))
      (node (ref "U1") (pin "H15") (pinfunction "GND_H15") (pintype "power_in"))
      (node (ref "U1") (pin "H16") (pinfunction "GND_H16") (pintype "power_in"))
      (node (ref "U1") (pin "H7") (pinfunction "GND_H7") (pintype "power_in"))
      (node (ref "U1") (pin "H8") (pinfunction "GND_H8") (pintype "power_in"))
      (node (ref "U1") (pin "H9") (pinfunction "GND_H9") (pintype "power_in"))
      (node (ref "U1") (pin "J10") (pinfunction "GND_J10") (pintype "power_in"))
      (node (ref "U1") (pin "J7") (pinfunction "GND_J7") (pintype "power_in"))
      (node (ref "U1") (pin "J8") (pinfunction "GND_J8") (pintype "power_in"))
      (node (ref "U1") (pin "J9") (pinfunction "GND_J9") (pintype "power_in"))
      (node (ref "U1") (pin "K13") (pinfunction "GND_K13") (pintype "power_in"))
      (node (ref "U1") (pin "K4") (pinfunction "GND_K4") (pintype "power_in"))
      (node (ref "U1") (pin "M13") (pinfunction "GND_M13") (pintype "power_in"))
      (node (ref "U1") (pin "M4") (pinfunction "GND_M4") (pintype "power_in"))
      (node (ref "U1") (pin "M5") (pinfunction "GNDA1_M5") (pintype "power_in"))
      (node (ref "U1") (pin "N10") (pinfunction "GND_N10") (pintype "power_in"))
      (node (ref "U1") (pin "N7") (pinfunction "GND_N7") (pintype "power_in"))
      (node (ref "U1") (pin "P12") (pinfunction "GND_P12") (pintype "power_in"))
      (node (ref "U1") (pin "P5") (pinfunction "GND_P5") (pintype "power_in"))
      (node (ref "U1") (pin "R15") (pinfunction "GND_R15") (pintype "power_in"))
      (node (ref "U1") (pin "R2") (pinfunction "GND_R2") (pintype "power_in"))
      (node (ref "U2") (pin "4") (pinfunction "VSS_4") (pintype "power_in"))
      (node (ref "XTAL1") (pin "2") (pinfunction "GND_2") (pintype "passive"))
    )
    (net (code "182") (name "Net-(U1J-CONF_DONE)") (class "Default")
      (node (ref "R5") (pin "2") (pintype "passive"))
      (node (ref "U1") (pin "H14") (pinfunction "CONF_DONE_H14") (pintype "bidirectional"))
    )
    (net (code "183") (name "Net-(U1J-nCE)") (class "Default")
      (node (ref "R4") (pin "2") (pintype "passive"))
      (node (ref "U1") (pin "J3") (pinfunction "nCE_J3") (pintype "input"))
    )
    (net (code "184") (name "Net-(U1J-nCONFIG)") (class "Default")
      (node (ref "R6") (pin "2") (pintype "passive"))
      (node (ref "U1") (pin "H5") (pinfunction "nCONFIG_H5") (pintype "input"))
    )
    (net (code "185") (name "Net-(U1J-nSTATUS)") (class "Default")
      (node (ref "R7") (pin "2") (pintype "passive"))
      (node (ref "U1") (pin "F4") (pinfunction "nSTATUS_F4") (pintype "bidirectional"))
    )
    (net (code "186") (name "VCC1V2") (class "Default")
      (node (ref "C1") (pin "1") (pinfunction "1_1") (pintype "passive"))
      (node (ref "C2") (pin "1") (pinfunction "1_1") (pintype "passive"))
      (node (ref "C3") (pin "1") (pinfunction "1_1") (pintype "passive"))
      (node (ref "C4") (pin "1") (pinfunction "1_1") (pintype "passive"))
      (node (ref "C5") (pin "1") (pinfunction "1_1") (pintype "passive"))
      (node (ref "U1") (pin "D13") (pinfunction "VCCD_PLL2_D13") (pintype "power_in"))
      (node (ref "U1") (pin "G10") (pinfunction "VCCINT_G10") (pintype "power_in"))
      (node (ref "U1") (pin "G6") (pinfunction "VCCINT_G6") (pintype "power_in"))
      (node (ref "U1") (pin "G7") (pinfunction "VCCINT_G7") (pintype "power_in"))
      (node (ref "U1") (pin "G8") (pinfunction "VCCINT_G8") (pintype "power_in"))
      (node (ref "U1") (pin "G9") (pinfunction "VCCINT_G9") (pintype "power_in"))
      (node (ref "U1") (pin "H11") (pinfunction "VCCINT_H11") (pintype "power_in"))
      (node (ref "U1") (pin "H6") (pinfunction "VCCINT_H6") (pintype "power_in"))
      (node (ref "U1") (pin "K7") (pinfunction "VCCINT_K7") (pintype "power_in"))
      (node (ref "U1") (pin "N4") (pinfunction "VCCD_PLL1_N4") (pintype "power_in"))
    )
    (net (code "187") (name "VCC2V5") (class "Default")
      (node (ref "C23") (pin "1") (pinfunction "1_1") (pintype "passive"))
      (node (ref "C24") (pin "1") (pinfunction "1_1") (pintype "passive"))
      (node (ref "JTAG1") (pin "4") (pinfunction "VCC_4") (pintype "passive"))
      (node (ref "R1") (pin "1") (pintype "passive"))
      (node (ref "R3") (pin "1") (pintype "passive"))
      (node (ref "U1") (pin "F12") (pinfunction "VCCA2_F12") (pintype "power_in"))
      (node (ref "U1") (pin "H12") (pinfunction "MSEL1_H12") (pintype "input"))
      (node (ref "U1") (pin "L5") (pinfunction "VCCA1_L5") (pintype "power_in"))
    )
    (net (code "188") (name "VCC3V3") (class "Default")
      (node (ref "C10") (pin "1") (pinfunction "1_1") (pintype "passive"))
      (node (ref "C11") (pin "1") (pinfunction "1_1") (pintype "passive"))
      (node (ref "C12") (pin "1") (pinfunction "1_1") (pintype "passive"))
      (node (ref "C13") (pin "1") (pinfunction "1_1") (pintype "passive"))
      (node (ref "C14") (pin "1") (pinfunction "1_1") (pintype "passive"))
      (node (ref "C15") (pin "1") (pinfunction "1_1") (pintype "passive"))
      (node (ref "C16") (pin "1") (pinfunction "1_1") (pintype "passive"))
      (node (ref "C18") (pin "1") (pinfunction "1_1") (pintype "passive"))
      (node (ref "C19") (pin "1") (pinfunction "1_1") (pintype "passive"))
      (node (ref "C20") (pin "1") (pinfunction "1_1") (pintype "passive"))
      (node (ref "C21") (pin "1") (pinfunction "1_1") (pintype "passive"))
      (node (ref "C22") (pin "1") (pinfunction "1_1") (pintype "passive"))
      (node (ref "C25") (pin "1") (pinfunction "1_1") (pintype "passive"))
      (node (ref "C26") (pin "1") (pinfunction "1_1") (pintype "passive"))
      (node (ref "C6") (pin "1") (pinfunction "1_1") (pintype "passive"))
      (node (ref "C7") (pin "1") (pinfunction "1_1") (pintype "passive"))
      (node (ref "C8") (pin "1") (pinfunction "1_1") (pintype "passive"))
      (node (ref "C9") (pin "1") (pinfunction "1_1") (pintype "passive"))
      (node (ref "R5") (pin "1") (pintype "passive"))
      (node (ref "R6") (pin "1") (pintype "passive"))
      (node (ref "R7") (pin "1") (pintype "passive"))
      (node (ref "U1") (pin "A1") (pinfunction "VCCIO8_A1") (pintype "power_in"))
      (node (ref "U1") (pin "A16") (pinfunction "VCCIO7_A16") (pintype "power_in"))
      (node (ref "U1") (pin "C10") (pinfunction "VCCIO7_C10") (pintype "power_in"))
      (node (ref "U1") (pin "C13") (pinfunction "VCCIO7_C13") (pintype "power_in"))
      (node (ref "U1") (pin "C4") (pinfunction "VCCIO8_C4") (pintype "power_in"))
      (node (ref "U1") (pin "C7") (pinfunction "VCCIO8_C7") (pintype "power_in"))
      (node (ref "U1") (pin "E14") (pinfunction "VCCIO6_E14") (pintype "power_in"))
      (node (ref "U1") (pin "E3") (pinfunction "VCCIO1_E3") (pintype "power_in"))
      (node (ref "U1") (pin "G14") (pinfunction "VCCIO6_G14") (pintype "power_in"))
      (node (ref "U1") (pin "G3") (pinfunction "VCCIO1_G3") (pintype "power_in"))
      (node (ref "U1") (pin "K14") (pinfunction "VCCIO5_K14") (pintype "power_in"))
      (node (ref "U1") (pin "K3") (pinfunction "VCCIO2_K3") (pintype "power_in"))
      (node (ref "U1") (pin "M14") (pinfunction "VCCIO5_M14") (pintype "power_in"))
      (node (ref "U1") (pin "M3") (pinfunction "VCCIO2_M3") (pintype "power_in"))
      (node (ref "U1") (pin "P10") (pinfunction "VCCIO4_P10") (pintype "power_in"))
      (node (ref "U1") (pin "P13") (pinfunction "VCCIO4_P13") (pintype "power_in"))
      (node (ref "U1") (pin "P4") (pinfunction "VCCIO3_P4") (pintype "power_in"))
      (node (ref "U1") (pin "P7") (pinfunction "VCCIO3_P7") (pintype "power_in"))
      (node (ref "U1") (pin "T1") (pinfunction "VCCIO3_T1") (pintype "power_in"))
      (node (ref "U1") (pin "T16") (pinfunction "VCCIO4_T16") (pintype "power_in"))
      (node (ref "U2") (pin "3") (pinfunction "~{W}_3") (pintype "input"))
      (node (ref "U2") (pin "7") (pinfunction "~{HOLD}_7") (pintype "input"))
      (node (ref "U2") (pin "8") (pinfunction "VCC_8") (pintype "power_in"))
      (node (ref "XTAL1") (pin "4") (pinfunction "VCC_4") (pintype "passive"))
    )
    (net (code "189") (name "unconnected-(JTAG1-NC-Pad6)") (class "Default")
      (node (ref "JTAG1") (pin "6") (pinfunction "NC_6") (pintype "passive+no_connect"))
    )
    (net (code "190") (name "unconnected-(JTAG1-NC-Pad7)") (class "Default")
      (node (ref "JTAG1") (pin "7") (pinfunction "NC_7") (pintype "passive+no_connect"))
    )
    (net (code "191") (name "unconnected-(JTAG1-NC-Pad8)") (class "Default")
      (node (ref "JTAG1") (pin "8") (pinfunction "NC_8") (pintype "passive+no_connect"))
    )
    (net (code "192") (name "unconnected-(U1B-IO-PadJ6)") (class "Default")
      (node (ref "U1") (pin "J6") (pinfunction "IO_J6") (pintype "bidirectional+no_connect"))
    )
    (net (code "193") (name "unconnected-(U1D-IO,_RDN2-PadN11)") (class "Default")
      (node (ref "U1") (pin "N11") (pinfunction "IO,_RDN2_N11") (pintype "bidirectional+no_connect"))
    )
    (net (code "194") (name "unconnected-(U1D-IO,_VREFB4N0-PadP11)") (class "Default")
      (node (ref "U1") (pin "P11") (pinfunction "IO,_VREFB4N0_P11") (pintype "bidirectional+no_connect"))
    )
    (net (code "195") (name "unconnected-(U1E-IO-PadN13)") (class "Default")
      (node (ref "U1") (pin "N13") (pinfunction "IO_N13") (pintype "bidirectional+no_connect"))
    )
    (net (code "196") (name "unconnected-(XTAL1-NC-Pad1)") (class "Default")
      (node (ref "XTAL1") (pin "1") (pinfunction "NC_1") (pintype "passive+no_connect"))
    )
  )
)
